# VEML6035.net
KiCad netlist of a schematic drawn in EAGLE
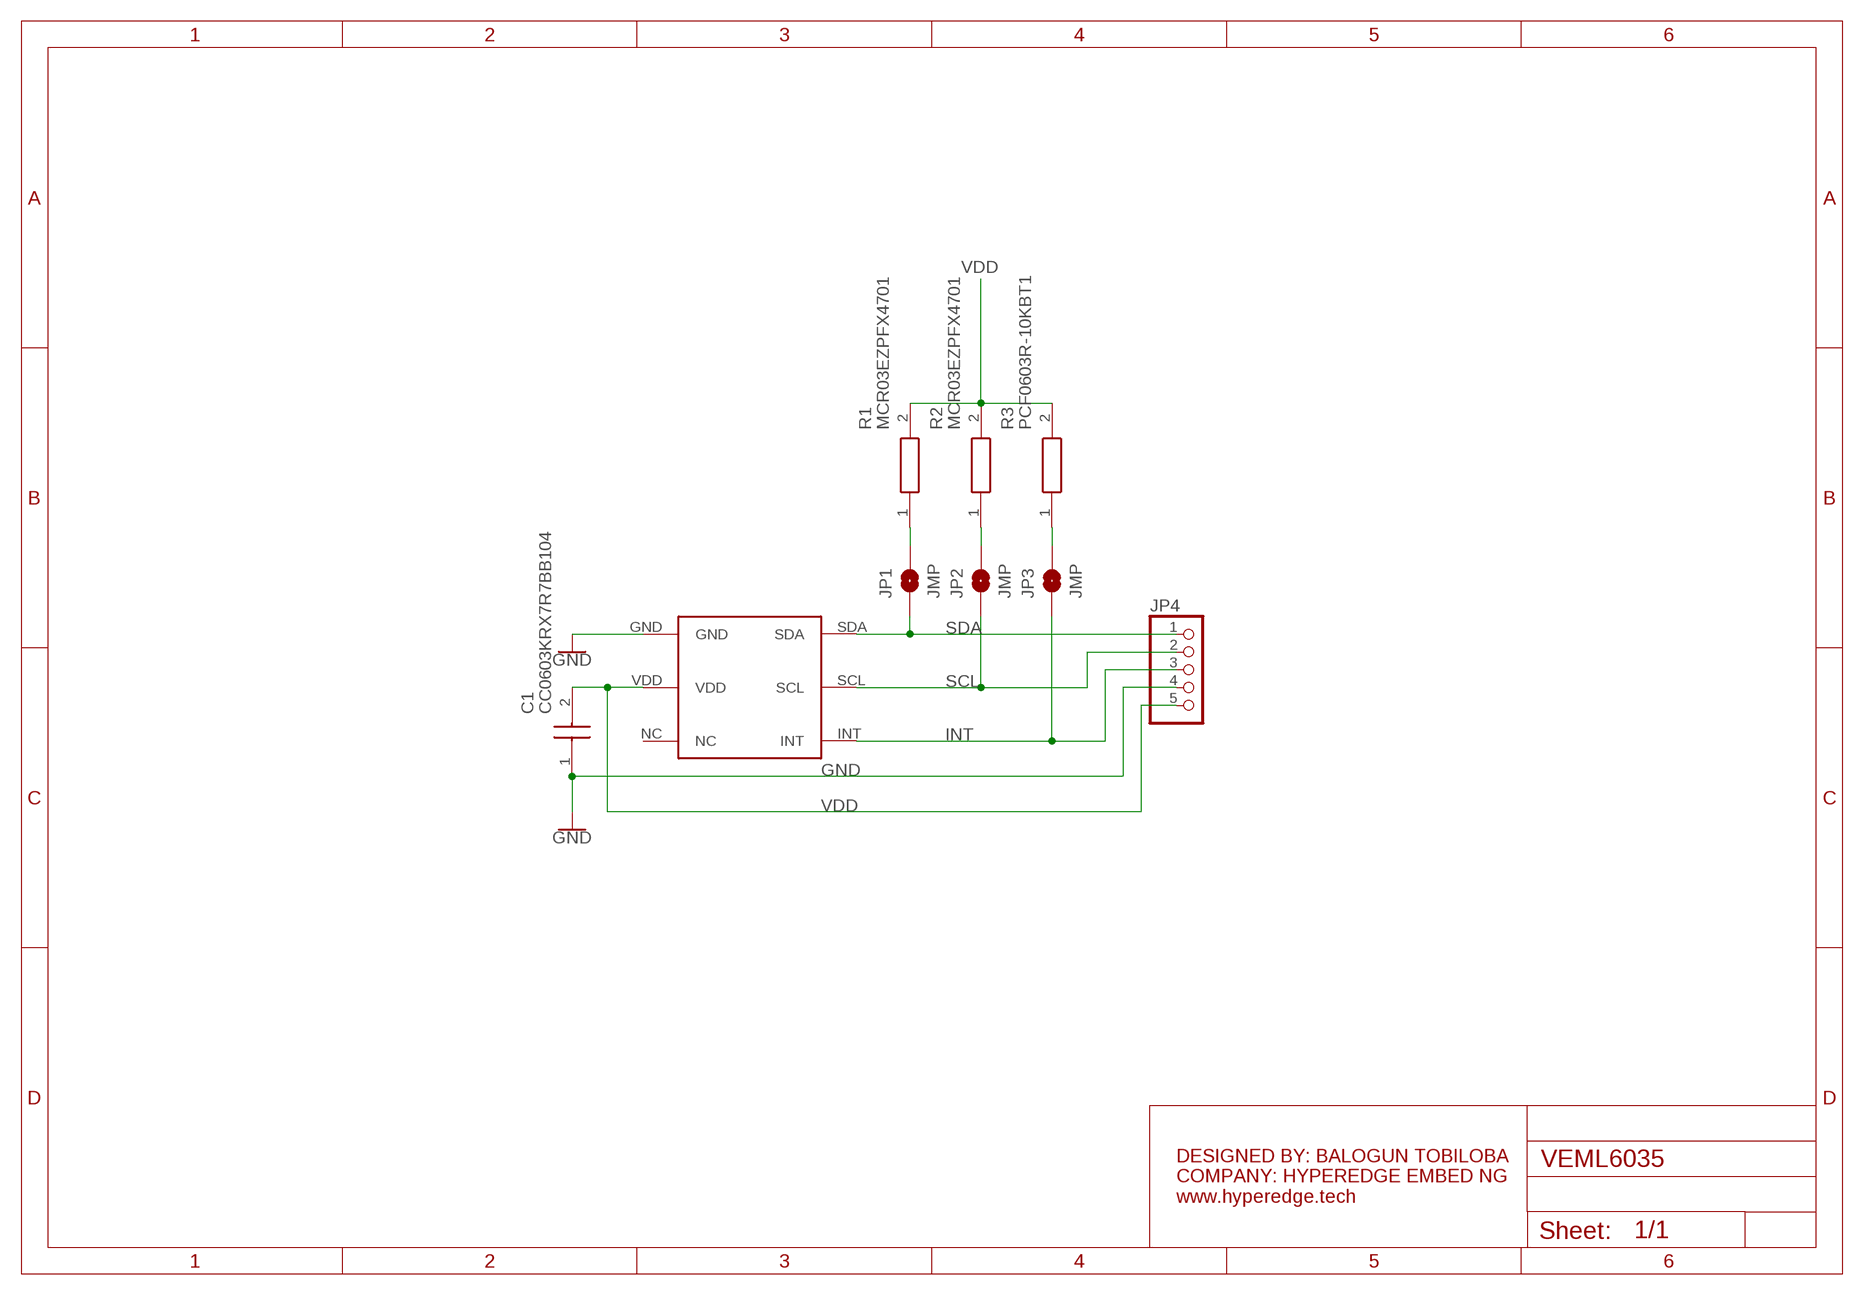
[diagram p0: schematic, sheet 1]

(export (version "E")
  (design (tool "Eeschema 10.0.6"))
  (components
    (comp (ref "C1")
      (value "CC0603KRX7R7BB104")
      (footprint "eagle-import:CAPC1608X90N")
      (fields
        (field (name "MOUSER_PART_NUMBER") "603-CC603KRX7R7BB104")
        (field (name "RS_PART_NUMBER") "6698763")
      )
      (libsource (lib "eagle-import") (part "CC0603KRX7R7BB104"))
    )
    (comp (ref "JP1")
      (value "JMP")
      (footprint "eagle-import:SMT-JUMPER_2_NO_NO-SILK")
      (libsource (lib "eagle-import") (part "JUMPER-SMT_2_NO_NO-SILK"))
    )
    (comp (ref "JP2")
      (value "JMP")
      (footprint "eagle-import:SMT-JUMPER_2_NO_NO-SILK")
      (libsource (lib "eagle-import") (part "JUMPER-SMT_2_NO_NO-SILK"))
    )
    (comp (ref "JP3")
      (value "JMP")
      (footprint "eagle-import:SMT-JUMPER_2_NO_NO-SILK")
      (libsource (lib "eagle-import") (part "JUMPER-SMT_2_NO_NO-SILK"))
    )
    (comp (ref "JP4")
      (value "PINHD-1X5")
      (footprint "eagle-import:1X05")
      (libsource (lib "eagle-import") (part "PINHD-1X5"))
    )
    (comp (ref "R1")
      (value "MCR03EZPFX4701")
      (footprint "eagle-import:RESC1608X55N")
      (fields (field (name "RS_PART_NUMBER") "9013581"))
      (libsource (lib "eagle-import") (part "MCR03EZPFX4701"))
    )
    (comp (ref "R2")
      (value "MCR03EZPFX4701")
      (footprint "eagle-import:RESC1608X55N")
      (fields (field (name "RS_PART_NUMBER") "9013581"))
      (libsource (lib "eagle-import") (part "MCR03EZPFX4701"))
    )
    (comp (ref "R3")
      (value "PCF0603R-10KBT1")
      (footprint "eagle-import:RESC1608X65N")
      (fields (field (name "MOUSER_PART_NUMBER") "756-PCF0603R-10KBT1"))
      (libsource (lib "eagle-import") (part "PCF0603R-10KBT1"))
    )
    (comp (ref "U$1")
      (value "VEML6035")
      (footprint "eagle-import:VEML6035")
      (libsource (lib "eagle-import") (part "VEML6035"))
    )
  )
  (nets
    (net (code "1") (name "/INT") (class "Default")
      (node (ref "JP3") (pin "1") (pinfunction "1_1") (pintype "passive"))
      (node (ref "JP4") (pin "3") (pinfunction "3_3") (pintype "passive"))
      (node (ref "U$1") (pin "INT") (pinfunction "INT_INT") (pintype "bidirectional"))
    )
    (net (code "2") (name "/SCL") (class "Default")
      (node (ref "JP2") (pin "1") (pinfunction "1_1") (pintype "passive"))
      (node (ref "JP4") (pin "2") (pinfunction "2_2") (pintype "passive"))
      (node (ref "U$1") (pin "SCL") (pinfunction "SCL_SCL") (pintype "bidirectional"))
    )
    (net (code "3") (name "/SDA") (class "Default")
      (node (ref "JP1") (pin "1") (pinfunction "1_1") (pintype "passive"))
      (node (ref "JP4") (pin "1") (pinfunction "1_1") (pintype "passive"))
      (node (ref "U$1") (pin "SDA") (pinfunction "SDA_SDA") (pintype "bidirectional"))
    )
    (net (code "4") (name "/VDD") (class "Default")
      (node (ref "C1") (pin "2") (pinfunction "C2_2") (pintype "bidirectional"))
      (node (ref "JP4") (pin "5") (pinfunction "5_5") (pintype "passive"))
      (node (ref "R1") (pin "2") (pinfunction "2_2") (pintype "bidirectional"))
      (node (ref "R2") (pin "2") (pinfunction "2_2") (pintype "bidirectional"))
      (node (ref "R3") (pin "2") (pinfunction "2_2") (pintype "bidirectional"))
      (node (ref "U$1") (pin "VDD") (pinfunction "VDD_VDD") (pintype "bidirectional"))
    )
    (net (code "5") (name "GND") (class "Default")
      (node (ref "C1") (pin "1") (pinfunction "C1_1") (pintype "bidirectional"))
      (node (ref "JP4") (pin "4") (pinfunction "4_4") (pintype "passive"))
      (node (ref "U$1") (pin "GND") (pinfunction "GND_GND") (pintype "bidirectional"))
    )
    (net (code "6") (name "Net-(JP1-Pad2)") (class "Default")
      (node (ref "JP1") (pin "2") (pinfunction "2_2") (pintype "passive"))
      (node (ref "R1") (pin "1") (pinfunction "1_1") (pintype "bidirectional"))
    )
    (net (code "7") (name "Net-(JP2-Pad2)") (class "Default")
      (node (ref "JP2") (pin "2") (pinfunction "2_2") (pintype "passive"))
      (node (ref "R2") (pin "1") (pinfunction "1_1") (pintype "bidirectional"))
    )
    (net (code "8") (name "Net-(JP3-Pad2)") (class "Default")
      (node (ref "JP3") (pin "2") (pinfunction "2_2") (pintype "passive"))
      (node (ref "R3") (pin "1") (pinfunction "1_1") (pintype "bidirectional"))
    )
    (net (code "9") (name "unconnected-(U$1-PadNC)") (class "Default")
      (node (ref "U$1") (pin "NC") (pinfunction "NC_NC") (pintype "bidirectional"))
    )
  )
)
